# Sheet7.net
KiCad netlist of a schematic drawn in Altium Designer
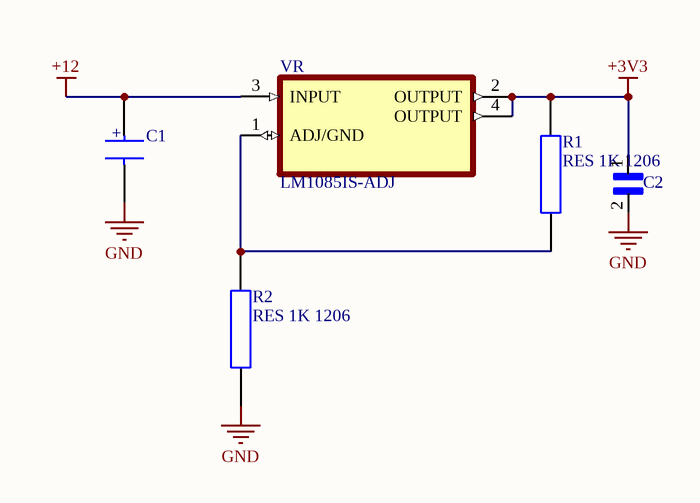
[diagram p0: Sheet7.SchDoc]

(export (version "E")
  (design (tool "Eeschema 10.0.6"))
  (components
    (comp (ref "C1")
      (value "CAP 100nF 0805")
      (footprint "CAP_805")
      (description "0805 smd")
      (libsource (lib "Udemy_Schlib1") (part "CAP 100nF 0805"))
    )
    (comp (ref "C2")
      (value "T491C106K025AT")
      (footprint "CAPPC6032X280N")
      (description "10 ÂµF Molded Tantalum Capacitors 25 V 2312 (6032 Metric) 1.5Ohm")
      (fields (field (name "MF") "KEMET"))
      (libsource (lib "T491C106K025AT") (part "T491C106K025AT"))
    )
    (comp (ref "R1")
      (value "RES 1K 1206")
      (footprint "RES_1206")
      (libsource (lib "Udemy_Schlib1") (part "RES 1K 1206"))
    )
    (comp (ref "R2")
      (value "RES 1K 1206")
      (footprint "RES_1206")
      (libsource (lib "Udemy_Schlib1") (part "RES 1K 1206"))
    )
    (comp (ref "VR")
      (value "LM1085IS-ADJ")
      (footprint "TO254P1524X483-4N")
      (description "3-A, 29-V, linear voltage regulator 3-DDPAK/TO-263")
      (fields (field (name "MF") "Texas Instruments"))
      (libsource (lib "LM1085IS-ADJ") (part "LM1085IS-ADJ"))
    )
  )
  (nets
    (net (code "1") (name "+3V3") (class "Default")
      (node (ref "C2") (pin "1") (pinfunction "1_1") (pintype "passive"))
      (node (ref "R1") (pin "2") (pintype "passive"))
      (node (ref "VR") (pin "2") (pinfunction "OUTPUT_2") (pintype "output"))
      (node (ref "VR") (pin "4") (pinfunction "OUTPUT_4") (pintype "output"))
    )
    (net (code "2") (name "+12") (class "Default")
      (node (ref "C1") (pin "1") (pinfunction "1_1") (pintype "passive"))
      (node (ref "VR") (pin "3") (pinfunction "INPUT_3") (pintype "input"))
    )
    (net (code "3") (name "GND") (class "Default")
      (node (ref "C1") (pin "2") (pinfunction "2_2") (pintype "passive"))
      (node (ref "C2") (pin "2") (pinfunction "2_2") (pintype "passive"))
      (node (ref "R2") (pin "1") (pintype "passive"))
    )
    (net (code "4") (name "Net-(VR-ADJ{slash}GND)") (class "Default")
      (node (ref "R1") (pin "1") (pintype "passive"))
      (node (ref "R2") (pin "2") (pintype "passive"))
      (node (ref "VR") (pin "1") (pinfunction "ADJ/GND_1") (pintype "bidirectional"))
    )
  )
)
